# KGM_Feedback_v2_1.net
KiCad netlist of a schematic drawn in EAGLE
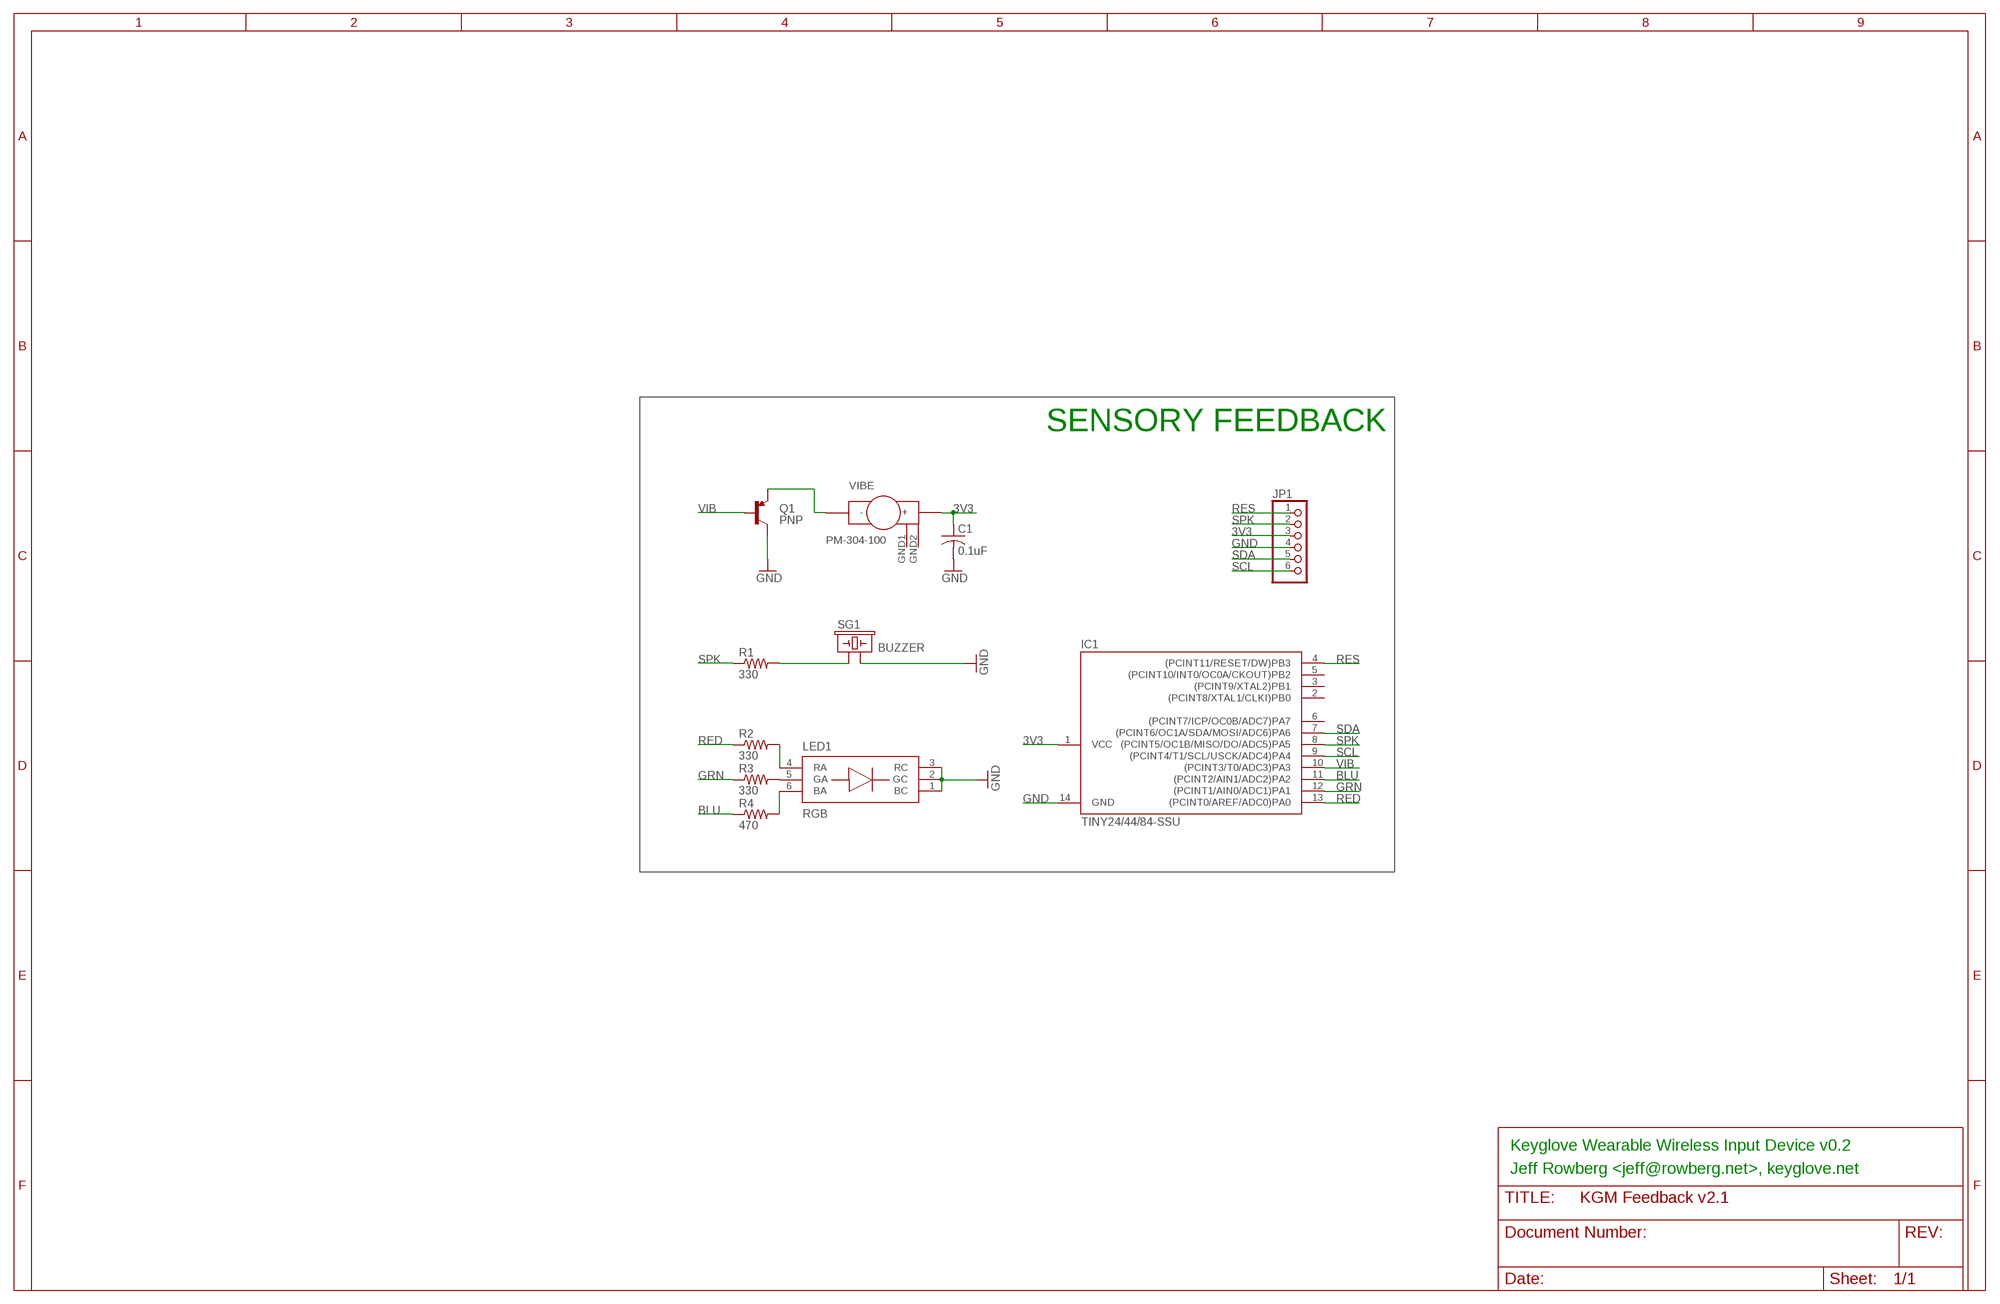
[diagram p0: schematic, sheet 1]

(export (version "E")
  (design (tool "Eeschema 10.0.6"))
  (components
    (comp (ref "C1")
      (value "0.1uF")
      (footprint "eagle-import:C0603")
      (libsource (lib "eagle-import") (part "C-USC0603"))
    )
    (comp (ref "IC1")
      (value "TINY24/44/84-SSU")
      (footprint "eagle-import:SOIC14")
      (libsource (lib "eagle-import") (part "TINY24/44/84-SSU"))
    )
    (comp (ref "JP1")
      (value "PINHD-1X6")
      (footprint "eagle-import:1X06")
      (libsource (lib "eagle-import") (part "PINHD-1X6"))
    )
    (comp (ref "LED1")
      (value "RGB")
      (footprint "eagle-import:PLCC-6")
      (libsource (lib "eagle-import") (part "ASMT-YTB2"))
    )
    (comp (ref "Q1")
      (value "PNP")
      (footprint "eagle-import:SOT23-3")
      (libsource (lib "eagle-import") (part "TRANSISTOR_PNPSMD"))
    )
    (comp (ref "R1")
      (value "330")
      (footprint "eagle-import:R0603")
      (libsource (lib "eagle-import") (part "R-US_R0603"))
    )
    (comp (ref "R2")
      (value "330")
      (footprint "eagle-import:R0603")
      (libsource (lib "eagle-import") (part "R-US_R0603"))
    )
    (comp (ref "R3")
      (value "330")
      (footprint "eagle-import:R0603")
      (libsource (lib "eagle-import") (part "R-US_R0603"))
    )
    (comp (ref "R4")
      (value "470")
      (footprint "eagle-import:R0603")
      (libsource (lib "eagle-import") (part "R-US_R0603"))
    )
    (comp (ref "SG1")
      (value "BUZZER")
      (footprint "eagle-import:BUZZER-CMT1102")
      (libsource (lib "eagle-import") (part "BUZZERSMD3"))
    )
    (comp (ref "VIBE")
      (value "PM-304-100")
      (footprint "eagle-import:PM-304-100")
      (libsource (lib "eagle-import") (part "PM-304-100"))
    )
  )
  (nets
    (net (code "1") (name "/3V3") (class "Default")
      (node (ref "C1") (pin "1") (pinfunction "1_1") (pintype "passive"))
      (node (ref "IC1") (pin "1") (pinfunction "VCC_1") (pintype "power_in"))
      (node (ref "JP1") (pin "3") (pinfunction "3_3") (pintype "passive"))
      (node (ref "VIBE") (pin "+") (pinfunction "+_+") (pintype "bidirectional"))
    )
    (net (code "2") (name "/BLU") (class "Default")
      (node (ref "IC1") (pin "11") (pinfunction "(PCINT2/AIN1/ADC2)PA2_11") (pintype "bidirectional"))
      (node (ref "R4") (pin "1") (pinfunction "1_1") (pintype "passive"))
    )
    (net (code "3") (name "/GRN") (class "Default")
      (node (ref "IC1") (pin "12") (pinfunction "(PCINT1/AIN0/ADC1)PA1_12") (pintype "bidirectional"))
      (node (ref "R3") (pin "1") (pinfunction "1_1") (pintype "passive"))
    )
    (net (code "4") (name "/RED") (class "Default")
      (node (ref "IC1") (pin "13") (pinfunction "(PCINT0/AREF/ADC0)PA0_13") (pintype "bidirectional"))
      (node (ref "R2") (pin "1") (pinfunction "1_1") (pintype "passive"))
    )
    (net (code "5") (name "/RES") (class "Default")
      (node (ref "IC1") (pin "4") (pinfunction "(PCINT11/RESET/DW)PB3_4") (pintype "bidirectional"))
      (node (ref "JP1") (pin "1") (pinfunction "1_1") (pintype "passive"))
    )
    (net (code "6") (name "/SCL") (class "Default")
      (node (ref "IC1") (pin "9") (pinfunction "(PCINT4/T1/SCL/USCK/ADC4)PA4_9") (pintype "bidirectional"))
      (node (ref "JP1") (pin "6") (pinfunction "6_6") (pintype "passive"))
    )
    (net (code "7") (name "/SDA") (class "Default")
      (node (ref "IC1") (pin "7") (pinfunction "(PCINT6/OC1A/SDA/MOSI/ADC6)PA6_7") (pintype "bidirectional"))
      (node (ref "JP1") (pin "5") (pinfunction "5_5") (pintype "passive"))
    )
    (net (code "8") (name "/SPK") (class "Default")
      (node (ref "IC1") (pin "8") (pinfunction "(PCINT5/OC1B/MISO/DO/ADC5)PA5_8") (pintype "bidirectional"))
      (node (ref "JP1") (pin "2") (pinfunction "2_2") (pintype "passive"))
      (node (ref "R1") (pin "1") (pinfunction "1_1") (pintype "passive"))
    )
    (net (code "9") (name "/VIB") (class "Default")
      (node (ref "IC1") (pin "10") (pinfunction "(PCINT3/T0/ADC3)PA3_10") (pintype "bidirectional"))
      (node (ref "Q1") (pin "1") (pinfunction "B_1") (pintype "passive"))
    )
    (net (code "10") (name "GND") (class "Default")
      (node (ref "C1") (pin "2") (pinfunction "2_2") (pintype "passive"))
      (node (ref "IC1") (pin "14") (pinfunction "GND_14") (pintype "power_in"))
      (node (ref "JP1") (pin "4") (pinfunction "4_4") (pintype "passive"))
      (node (ref "LED1") (pin "1") (pinfunction "BC_1") (pintype "bidirectional"))
      (node (ref "LED1") (pin "2") (pinfunction "GC_2") (pintype "bidirectional"))
      (node (ref "LED1") (pin "3") (pinfunction "RC_3") (pintype "bidirectional"))
      (node (ref "Q1") (pin "3") (pinfunction "C_3") (pintype "passive"))
      (node (ref "SG1") (pin "2") (pinfunction "2_2") (pintype "passive"))
    )
    (net (code "11") (name "Net-(LED1-BA)") (class "Default")
      (node (ref "LED1") (pin "6") (pinfunction "BA_6") (pintype "bidirectional"))
      (node (ref "R4") (pin "2") (pinfunction "2_2") (pintype "passive"))
    )
    (net (code "12") (name "Net-(LED1-GA)") (class "Default")
      (node (ref "LED1") (pin "5") (pinfunction "GA_5") (pintype "bidirectional"))
      (node (ref "R3") (pin "2") (pinfunction "2_2") (pintype "passive"))
    )
    (net (code "13") (name "Net-(LED1-RA)") (class "Default")
      (node (ref "LED1") (pin "4") (pinfunction "RA_4") (pintype "bidirectional"))
      (node (ref "R2") (pin "2") (pinfunction "2_2") (pintype "passive"))
    )
    (net (code "14") (name "Net-(Q1-E)") (class "Default")
      (node (ref "Q1") (pin "2") (pinfunction "E_2") (pintype "passive"))
      (node (ref "VIBE") (pin "-") (pinfunction "-_-") (pintype "bidirectional"))
    )
    (net (code "15") (name "Net-(R1-Pad2)") (class "Default")
      (node (ref "R1") (pin "2") (pinfunction "2_2") (pintype "passive"))
      (node (ref "SG1") (pin "1") (pinfunction "1_1") (pintype "passive"))
    )
    (net (code "16") (name "unconnected-(IC1-(PCINT7{slash}ICP{slash}OC0B{slash}ADC7)PA7-Pad6)") (class "Default")
      (node (ref "IC1") (pin "6") (pinfunction "(PCINT7/ICP/OC0B/ADC7)PA7_6") (pintype "bidirectional"))
    )
    (net (code "17") (name "unconnected-(IC1-(PCINT8{slash}XTAL1{slash}CLKI)PB0-Pad2)") (class "Default")
      (node (ref "IC1") (pin "2") (pinfunction "(PCINT8/XTAL1/CLKI)PB0_2") (pintype "bidirectional"))
    )
    (net (code "18") (name "unconnected-(IC1-(PCINT9{slash}XTAL2)PB1-Pad3)") (class "Default")
      (node (ref "IC1") (pin "3") (pinfunction "(PCINT9/XTAL2)PB1_3") (pintype "bidirectional"))
    )
    (net (code "19") (name "unconnected-(IC1-(PCINT10{slash}INT0{slash}OC0A{slash}CKOUT)PB2-Pad5)") (class "Default")
      (node (ref "IC1") (pin "5") (pinfunction "(PCINT10/INT0/OC0A/CKOUT)PB2_5") (pintype "bidirectional"))
    )
    (net (code "20") (name "unconnected-(VIBE-GND-PadGND1)") (class "Default")
      (node (ref "VIBE") (pin "GND1") (pinfunction "GND_GND1") (pintype "bidirectional"))
    )
    (net (code "21") (name "unconnected-(VIBE-GND-PadGND2)") (class "Default")
      (node (ref "VIBE") (pin "GND2") (pinfunction "GND_GND2") (pintype "bidirectional"))
    )
  )
)
